# leds-2.net
KiCad netlist of a schematic drawn in EAGLE
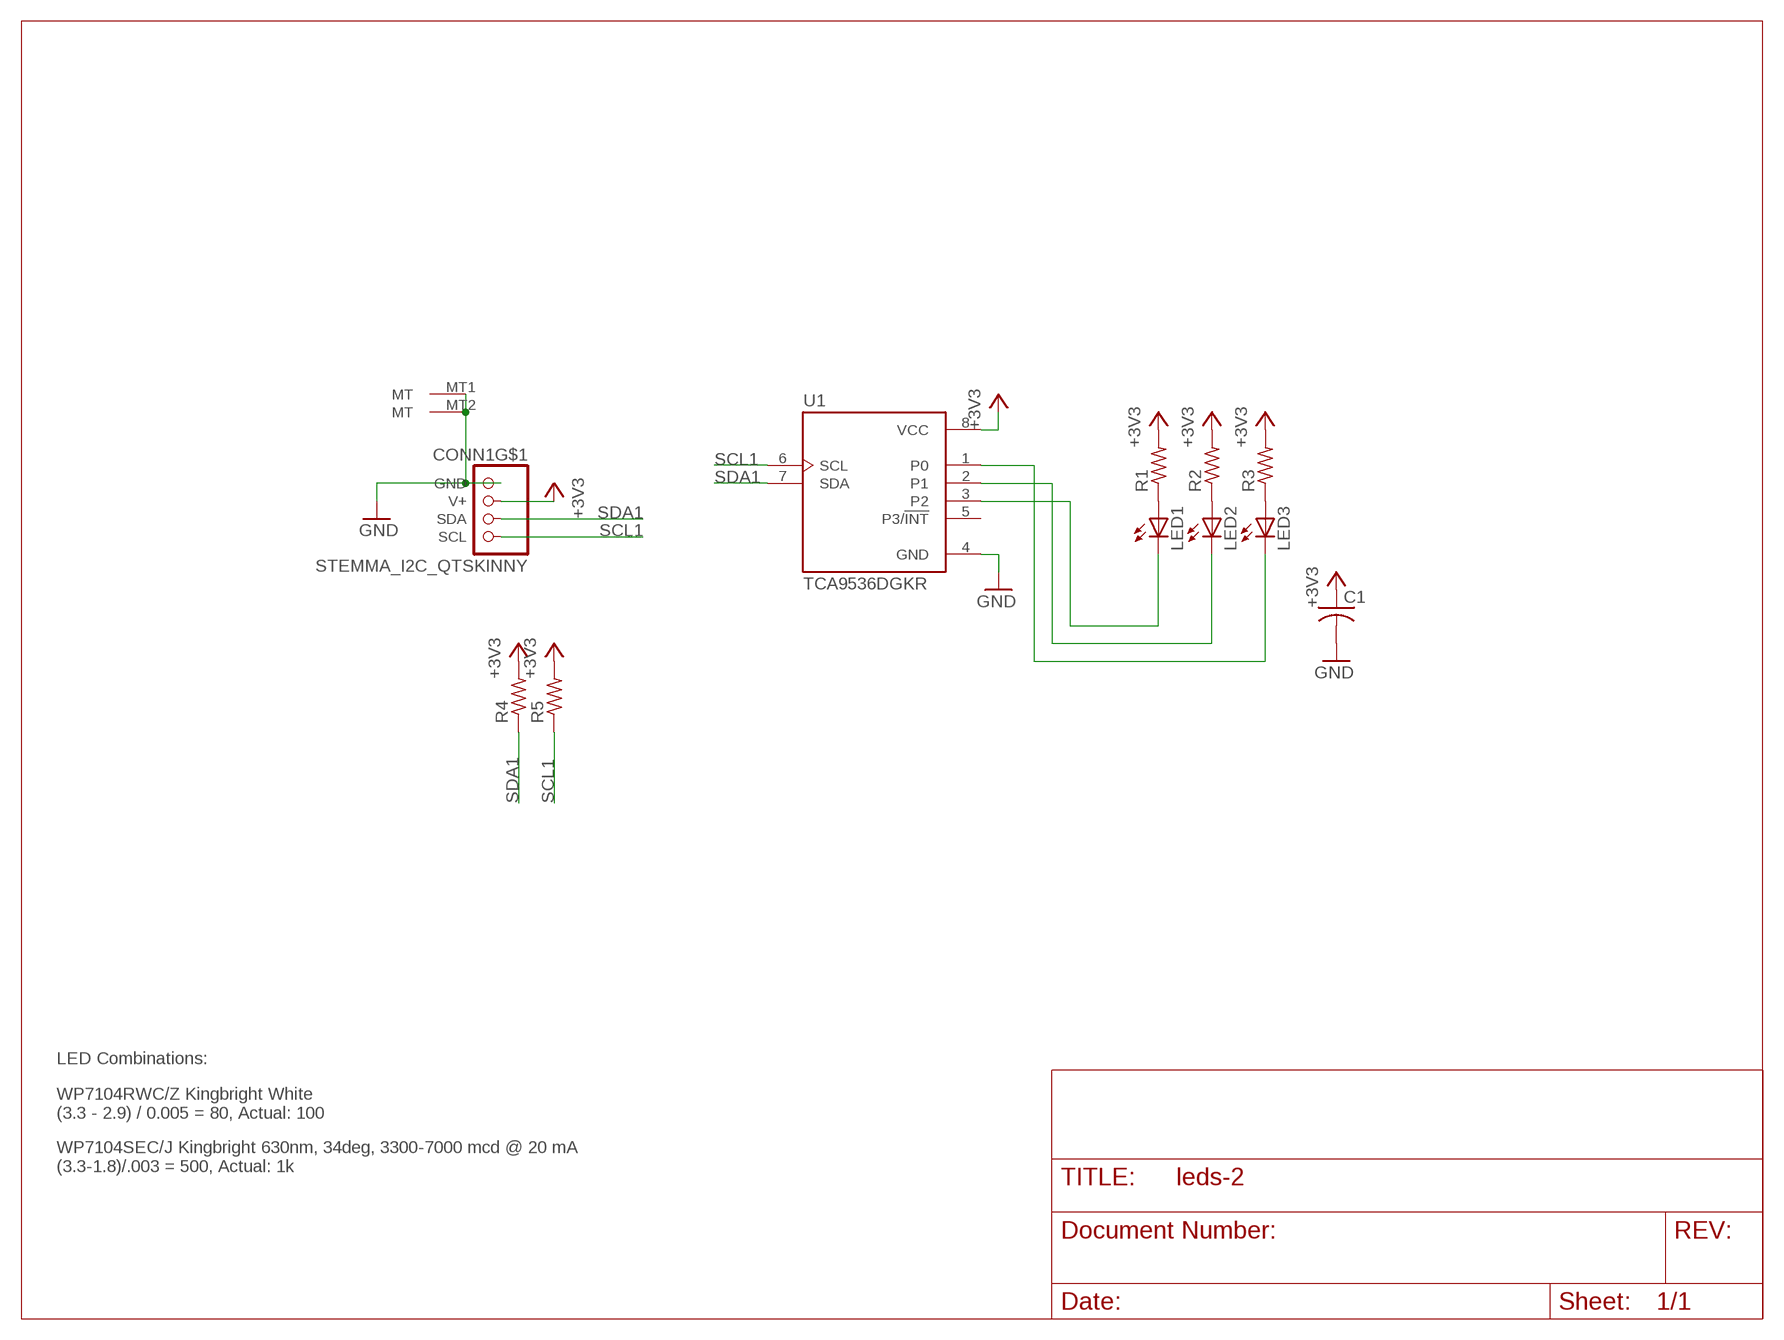
[diagram p0: schematic, sheet 1]

(export (version "E")
  (design (tool "Eeschema 10.0.6"))
  (components
    (comp (ref "C1")
      (value "C-USC0603K")
      (footprint "eagle-import:C0603K")
      (libsource (lib "eagle-import") (part "C-USC0603K"))
    )
    (comp (ref "CONN1")
      (value "STEMMA_I2C_QTSKINNY")
      (footprint "eagle-import:JST_SH4_SKINNY")
      (libsource (lib "eagle-import") (part "STEMMA_I2C_QTSKINNY"))
    )
    (comp (ref "LED1")
      (value "LED3MM")
      (footprint "eagle-import:LED3MM")
      (libsource (lib "eagle-import") (part "LED3MM"))
    )
    (comp (ref "LED2")
      (value "LED3MM")
      (footprint "eagle-import:LED3MM")
      (libsource (lib "eagle-import") (part "LED3MM"))
    )
    (comp (ref "LED3")
      (value "LED3MM")
      (footprint "eagle-import:LED3MM")
      (libsource (lib "eagle-import") (part "LED3MM"))
    )
    (comp (ref "R1")
      (value "R-US_R0603")
      (footprint "eagle-import:R0603")
      (libsource (lib "eagle-import") (part "R-US_R0603"))
    )
    (comp (ref "R2")
      (value "R-US_R0603")
      (footprint "eagle-import:R0603")
      (libsource (lib "eagle-import") (part "R-US_R0603"))
    )
    (comp (ref "R3")
      (value "R-US_R0603")
      (footprint "eagle-import:R0603")
      (libsource (lib "eagle-import") (part "R-US_R0603"))
    )
    (comp (ref "R4")
      (value "R-US_R0603")
      (footprint "eagle-import:R0603")
      (libsource (lib "eagle-import") (part "R-US_R0603"))
    )
    (comp (ref "R5")
      (value "R-US_R0603")
      (footprint "eagle-import:R0603")
      (libsource (lib "eagle-import") (part "R-US_R0603"))
    )
    (comp (ref "U1")
      (value "TCA9536DGKR")
      (footprint "eagle-import:SOP65P490X110-8N")
      (fields (field (name "MANUFACTURER") "Texas Instruments"))
      (libsource (lib "eagle-import") (part "TCA9536DGKR"))
    )
  )
  (nets
    (net (code "1") (name "+3V3") (class "Default")
      (node (ref "C1") (pin "1") (pinfunction "1_1") (pintype "passive"))
      (node (ref "CONN1") (pin "2") (pinfunction "V+_2") (pintype "passive"))
      (node (ref "R1") (pin "2") (pinfunction "2_2") (pintype "passive"))
      (node (ref "R2") (pin "2") (pinfunction "2_2") (pintype "passive"))
      (node (ref "R3") (pin "2") (pinfunction "2_2") (pintype "passive"))
      (node (ref "R4") (pin "2") (pinfunction "2_2") (pintype "passive"))
      (node (ref "R5") (pin "2") (pinfunction "2_2") (pintype "passive"))
      (node (ref "U1") (pin "8") (pinfunction "VCC_8") (pintype "power_in"))
    )
    (net (code "2") (name "/SCL1") (class "Default")
      (node (ref "CONN1") (pin "4") (pinfunction "SCL_4") (pintype "passive"))
      (node (ref "R5") (pin "1") (pinfunction "1_1") (pintype "passive"))
      (node (ref "U1") (pin "6") (pinfunction "SCL_6") (pintype "bidirectional"))
    )
    (net (code "3") (name "/SDA1") (class "Default")
      (node (ref "CONN1") (pin "3") (pinfunction "SDA_3") (pintype "passive"))
      (node (ref "R4") (pin "1") (pinfunction "1_1") (pintype "passive"))
      (node (ref "U1") (pin "7") (pinfunction "SDA_7") (pintype "bidirectional"))
    )
    (net (code "4") (name "GND") (class "Default")
      (node (ref "C1") (pin "2") (pinfunction "2_2") (pintype "passive"))
      (node (ref "CONN1") (pin "1") (pinfunction "GND_1") (pintype "passive"))
      (node (ref "CONN1") (pin "MT1") (pinfunction "MT_MT1") (pintype "bidirectional"))
      (node (ref "CONN1") (pin "MT2") (pinfunction "MT_MT2") (pintype "bidirectional"))
      (node (ref "U1") (pin "4") (pinfunction "GND_4") (pintype "power_in"))
    )
    (net (code "5") (name "Net-(LED1-C)") (class "Default")
      (node (ref "LED1") (pin "K") (pinfunction "C_K") (pintype "passive"))
      (node (ref "U1") (pin "3") (pinfunction "P2_3") (pintype "bidirectional"))
    )
    (net (code "6") (name "Net-(LED1-PadA)") (class "Default")
      (node (ref "LED1") (pin "A") (pinfunction "A_A") (pintype "passive"))
      (node (ref "R1") (pin "1") (pinfunction "1_1") (pintype "passive"))
    )
    (net (code "7") (name "Net-(LED2-C)") (class "Default")
      (node (ref "LED2") (pin "K") (pinfunction "C_K") (pintype "passive"))
      (node (ref "U1") (pin "2") (pinfunction "P1_2") (pintype "bidirectional"))
    )
    (net (code "8") (name "Net-(LED2-PadA)") (class "Default")
      (node (ref "LED2") (pin "A") (pinfunction "A_A") (pintype "passive"))
      (node (ref "R2") (pin "1") (pinfunction "1_1") (pintype "passive"))
    )
    (net (code "9") (name "Net-(LED3-C)") (class "Default")
      (node (ref "LED3") (pin "K") (pinfunction "C_K") (pintype "passive"))
      (node (ref "U1") (pin "1") (pinfunction "P0_1") (pintype "bidirectional"))
    )
    (net (code "10") (name "Net-(LED3-PadA)") (class "Default")
      (node (ref "LED3") (pin "A") (pinfunction "A_A") (pintype "passive"))
      (node (ref "R3") (pin "1") (pinfunction "1_1") (pintype "passive"))
    )
    (net (code "11") (name "unconnected-(U1-P3{slash}~{INT}-Pad5)") (class "Default")
      (node (ref "U1") (pin "5") (pinfunction "P3/~{INT}_5") (pintype "bidirectional"))
    )
  )
)
